# design.net
KiCad netlist of a schematic drawn in Altium Designer
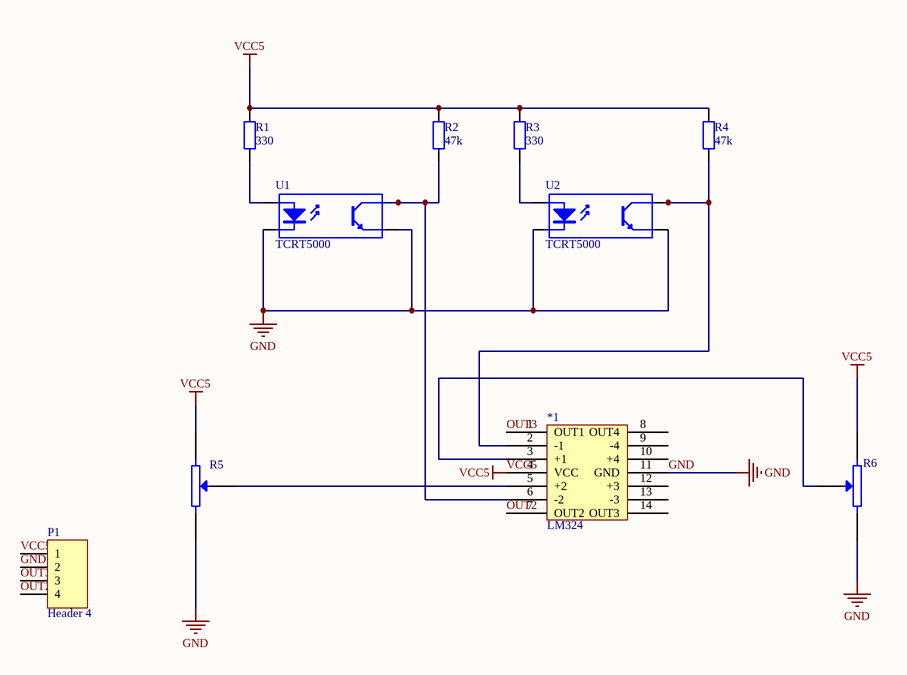
[diagram p0: 红外.SchDoc]

(export (version "E")
  (design (tool "Eeschema 10.0.6"))
  (components
    (comp (ref "*1") (value "LM324") (footprint "DIP14") (libsource (lib "ＳＴＣ８９Ｃ５２") (part "LM324")))
    (comp (ref "P1")
      (value "Header 4")
      (footprint "HDR1X4")
      (description "Header, 4-Pin")
      (fields (field (name "PUBLISHER") "Altium Limited"))
      (libsource (lib "Miscellaneous Connectors") (part "Header 4"))
    )
    (comp (ref "R1")
      (value "330")
      (footprint "AXIAL-0.4")
      (description "Resistor")
      (fields (field (name "Comment") "Res2") (field (name "PUBLISHER") "Altium Limited"))
      (libsource (lib "Miscellaneous Devices") (part "Res2"))
    )
    (comp (ref "R2")
      (value "47k")
      (footprint "AXIAL-0.4")
      (description "Resistor")
      (fields (field (name "Comment") "Res2") (field (name "PUBLISHER") "Altium Limited"))
      (libsource (lib "Miscellaneous Devices") (part "Res2"))
    )
    (comp (ref "R3")
      (value "330")
      (footprint "AXIAL-0.4")
      (description "Resistor")
      (fields (field (name "Comment") "Res2") (field (name "PUBLISHER") "Altium Limited"))
      (libsource (lib "Miscellaneous Devices") (part "Res2"))
    )
    (comp (ref "R4")
      (value "47k")
      (footprint "AXIAL-0.4")
      (description "Resistor")
      (fields (field (name "Comment") "Res2") (field (name "PUBLISHER") "Altium Limited"))
      (libsource (lib "Miscellaneous Devices") (part "Res2"))
    )
    (comp (ref "R5")
      (value "1K")
      (footprint "VR5")
      (description "Potentiometer")
      (libsource (lib "电阻") (part "RESVR"))
    )
    (comp (ref "R6")
      (value "1K")
      (footprint "VR5")
      (description "Potentiometer")
      (libsource (lib "电阻") (part "RESVR"))
    )
    (comp (ref "U1")
      (value "TCRT5000")
      (footprint "DIP-4")
      (description "4-Pin Phototransistor Optocoupler")
      (fields (field (name "PUBLISHER") "Altium Limited"))
      (libsource (lib "Miscellaneous Devices") (part "Optoisolator1"))
    )
    (comp (ref "U2")
      (value "TCRT5000")
      (footprint "DIP-4")
      (description "4-Pin Phototransistor Optocoupler")
      (fields (field (name "PUBLISHER") "Altium Limited"))
      (libsource (lib "Miscellaneous Devices") (part "Optoisolator1"))
    )
  )
  (nets
    (net (code "1") (name "/OUT2") (class "Default")
      (node (ref "*1") (pin "7") (pinfunction "OUT2_7") (pintype "passive"))
      (node (ref "P1") (pin "4") (pinfunction "4_4") (pintype "passive"))
    )
    (net (code "2") (name "/OUT3") (class "Default")
      (node (ref "*1") (pin "1") (pinfunction "OUT1_1") (pintype "passive"))
      (node (ref "P1") (pin "3") (pinfunction "3_3") (pintype "passive"))
    )
    (net (code "3") (name "GND") (class "Default")
      (node (ref "*1") (pin "11") (pinfunction "GND_11") (pintype "passive"))
      (node (ref "P1") (pin "2") (pinfunction "2_2") (pintype "passive"))
      (node (ref "R5") (pin "2") (pinfunction "2_2") (pintype "passive"))
      (node (ref "R6") (pin "1") (pinfunction "1_1") (pintype "passive"))
      (node (ref "U1") (pin "2") (pinfunction "K_2") (pintype "passive"))
      (node (ref "U1") (pin "3") (pinfunction "E_3") (pintype "passive"))
      (node (ref "U2") (pin "2") (pinfunction "K_2") (pintype "passive"))
      (node (ref "U2") (pin "3") (pinfunction "E_3") (pintype "passive"))
    )
    (net (code "4") (name "Net-(*1-+1)") (class "Default")
      (node (ref "*1") (pin "3") (pinfunction "+1_3") (pintype "passive"))
      (node (ref "R6") (pin "3") (pinfunction "W_3") (pintype "passive"))
    )
    (net (code "5") (name "Net-(*1-+2)") (class "Default")
      (node (ref "*1") (pin "5") (pinfunction "+2_5") (pintype "passive"))
      (node (ref "R5") (pin "3") (pinfunction "W_3") (pintype "passive"))
    )
    (net (code "6") (name "Net-(*1--1)") (class "Default")
      (node (ref "*1") (pin "2") (pinfunction "-1_2") (pintype "passive"))
      (node (ref "R4") (pin "1") (pinfunction "1_1") (pintype "passive"))
      (node (ref "U2") (pin "4") (pinfunction "C_4") (pintype "passive"))
    )
    (net (code "7") (name "Net-(*1--2)") (class "Default")
      (node (ref "*1") (pin "6") (pinfunction "-2_6") (pintype "passive"))
      (node (ref "R2") (pin "1") (pinfunction "1_1") (pintype "passive"))
      (node (ref "U1") (pin "4") (pinfunction "C_4") (pintype "passive"))
    )
    (net (code "8") (name "Net-(U1-A)") (class "Default")
      (node (ref "R1") (pin "1") (pinfunction "1_1") (pintype "passive"))
      (node (ref "U1") (pin "1") (pinfunction "A_1") (pintype "passive"))
    )
    (net (code "9") (name "Net-(U2-A)") (class "Default")
      (node (ref "R3") (pin "1") (pinfunction "1_1") (pintype "passive"))
      (node (ref "U2") (pin "1") (pinfunction "A_1") (pintype "passive"))
    )
    (net (code "10") (name "VCC5") (class "Default")
      (node (ref "*1") (pin "4") (pinfunction "VCC_4") (pintype "passive"))
      (node (ref "P1") (pin "1") (pinfunction "1_1") (pintype "passive"))
      (node (ref "R1") (pin "2") (pinfunction "2_2") (pintype "passive"))
      (node (ref "R2") (pin "2") (pinfunction "2_2") (pintype "passive"))
      (node (ref "R3") (pin "2") (pinfunction "2_2") (pintype "passive"))
      (node (ref "R4") (pin "2") (pinfunction "2_2") (pintype "passive"))
      (node (ref "R5") (pin "1") (pinfunction "1_1") (pintype "passive"))
      (node (ref "R6") (pin "2") (pinfunction "2_2") (pintype "passive"))
    )
    (net (code "11") (name "unconnected-(*1-+3-Pad12)") (class "Default")
      (node (ref "*1") (pin "12") (pinfunction "+3_12") (pintype "passive"))
    )
    (net (code "12") (name "unconnected-(*1-+4-Pad10)") (class "Default")
      (node (ref "*1") (pin "10") (pinfunction "+4_10") (pintype "passive"))
    )
    (net (code "13") (name "unconnected-(*1--3-Pad13)") (class "Default")
      (node (ref "*1") (pin "13") (pinfunction "-3_13") (pintype "passive"))
    )
    (net (code "14") (name "unconnected-(*1--4-Pad9)") (class "Default")
      (node (ref "*1") (pin "9") (pinfunction "-4_9") (pintype "passive"))
    )
    (net (code "15") (name "unconnected-(*1-OUT3-Pad14)") (class "Default")
      (node (ref "*1") (pin "14") (pinfunction "OUT3_14") (pintype "passive"))
    )
    (net (code "16") (name "unconnected-(*1-OUT4-Pad8)") (class "Default")
      (node (ref "*1") (pin "8") (pinfunction "OUT4_8") (pintype "passive"))
    )
  )
)
